# PCB-BI8-1x4SERCP_v08-16.net
KiCad netlist of a schematic drawn in EAGLE
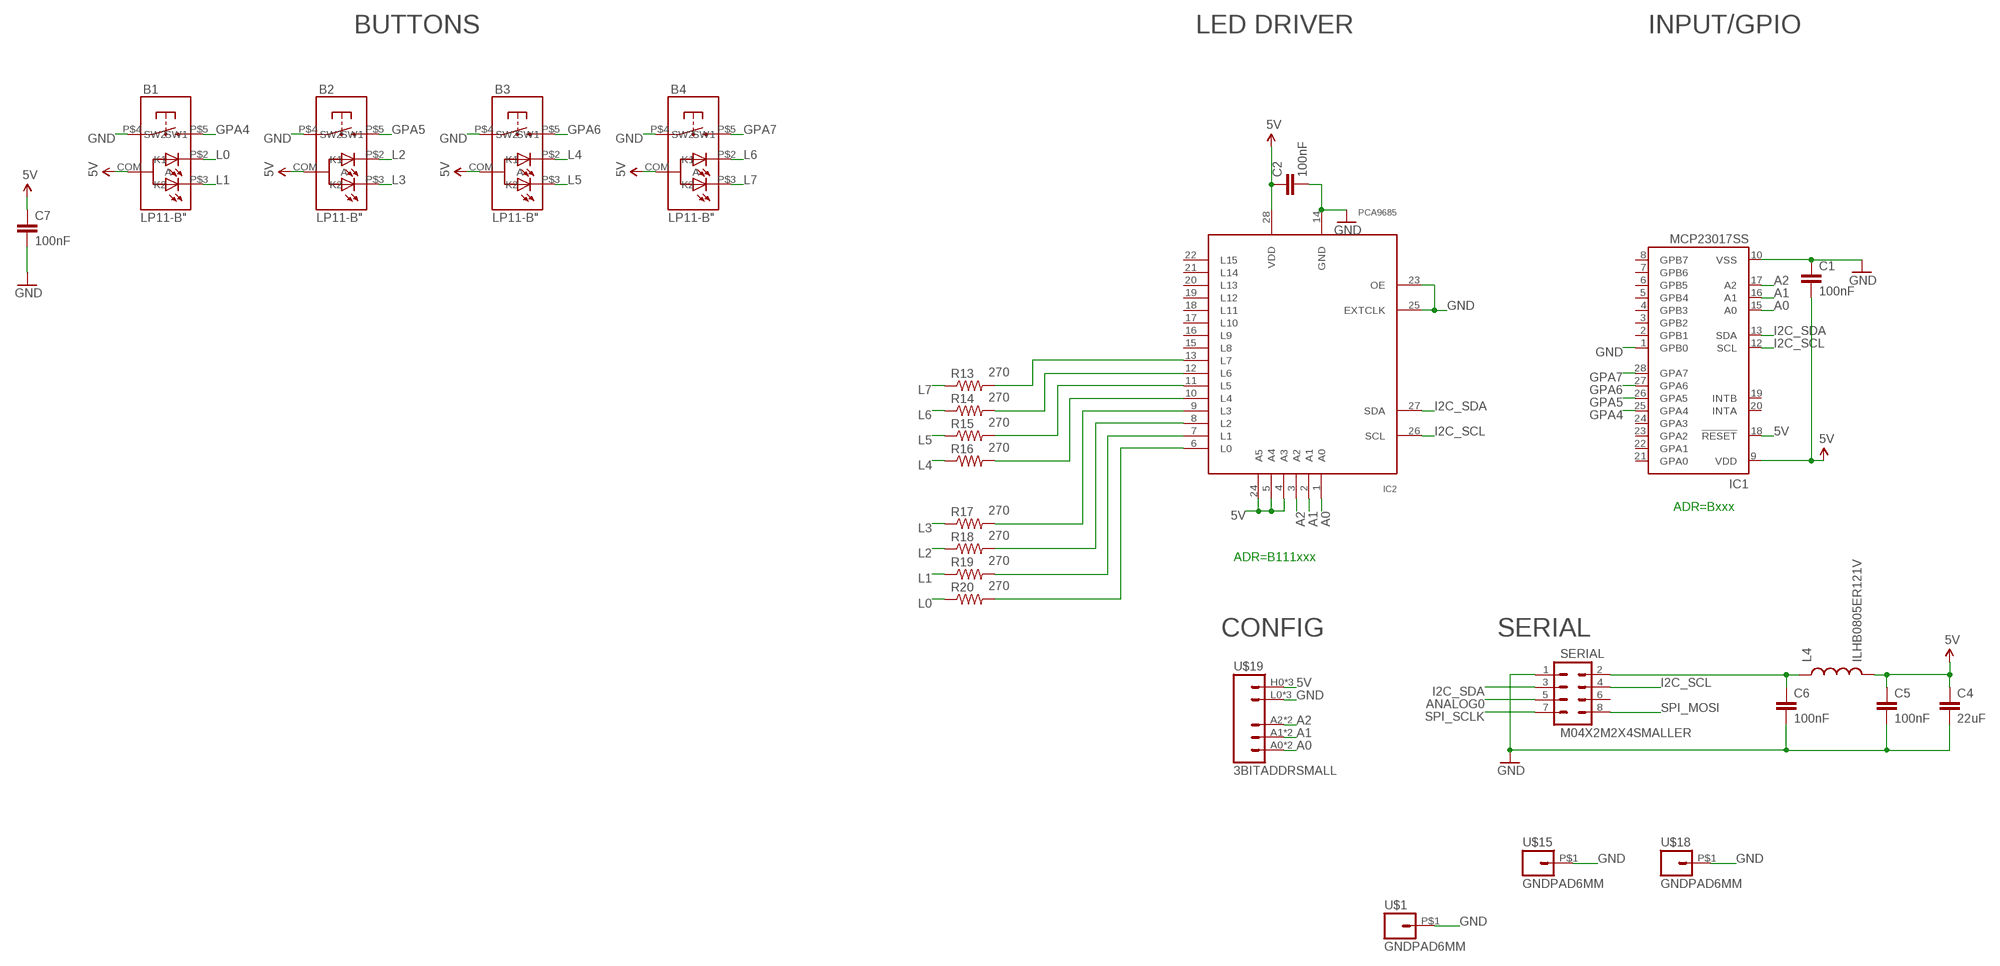
[diagram p0: schematic, sheet 1]

(export (version "E")
  (design (tool "Eeschema 10.0.6"))
  (components
    (comp (ref "B1")
      (value "LP11-B\"")
      (footprint "eagle-import:LP11")
      (libsource (lib "eagle-import") (part "LP11-B{dblquote}"))
    )
    (comp (ref "B2")
      (value "LP11-B\"")
      (footprint "eagle-import:LP11")
      (libsource (lib "eagle-import") (part "LP11-B{dblquote}"))
    )
    (comp (ref "B3")
      (value "LP11-B\"")
      (footprint "eagle-import:LP11")
      (libsource (lib "eagle-import") (part "LP11-B{dblquote}"))
    )
    (comp (ref "B4")
      (value "LP11-B\"")
      (footprint "eagle-import:LP11")
      (libsource (lib "eagle-import") (part "LP11-B{dblquote}"))
    )
    (comp (ref "C1")
      (value "100nF")
      (footprint "eagle-import:0603-CAP")
      (libsource (lib "eagle-import") (part "CAP0603-CAP"))
    )
    (comp (ref "C2")
      (value "100nF")
      (footprint "eagle-import:0603-CAP")
      (libsource (lib "eagle-import") (part "CAP0603-CAP"))
    )
    (comp (ref "C4")
      (value "22uF")
      (footprint "eagle-import:0805")
      (libsource (lib "eagle-import") (part "CAP0805"))
    )
    (comp (ref "C5")
      (value "100nF")
      (footprint "eagle-import:0603-CAP")
      (libsource (lib "eagle-import") (part "CAP0603-CAP"))
    )
    (comp (ref "C6")
      (value "100nF")
      (footprint "eagle-import:0603-CAP")
      (libsource (lib "eagle-import") (part "CAP0603-CAP"))
    )
    (comp (ref "C7")
      (value "100nF")
      (footprint "eagle-import:0603-CAP")
      (libsource (lib "eagle-import") (part "CAP0603-CAP"))
    )
    (comp (ref "IC1")
      (value "MCP23017SS")
      (footprint "eagle-import:SSOP28")
      (fields
        (field (name "MF") "MICROCHIP")
        (field (name "MPN") "MCP23017-E/SS")
        (field (name "MPN_1") "MCP23017-E/SS")
        (field (name "OC_FARNELL") "1467674")
        (field (name "OC_NEWARK") "31K2960")
      )
      (libsource (lib "eagle-import") (part "MCP23017SS"))
    )
    (comp (ref "IC2")
      (value "PCA9685")
      (footprint "eagle-import:TSSOP28")
      (libsource (lib "eagle-import") (part "PCA9685"))
    )
    (comp (ref "L4")
      (value "ILHB0805ER121V")
      (footprint "eagle-import:0805")
      (libsource (lib "eagle-import") (part "INDUCTOR0805"))
    )
    (comp (ref "R13")
      (value "270")
      (footprint "eagle-import:0603-RES")
      (libsource (lib "eagle-import") (part "RESISTOR0603-RES"))
    )
    (comp (ref "R14")
      (value "270")
      (footprint "eagle-import:0603-RES")
      (libsource (lib "eagle-import") (part "RESISTOR0603-RES"))
    )
    (comp (ref "R15")
      (value "270")
      (footprint "eagle-import:0603-RES")
      (libsource (lib "eagle-import") (part "RESISTOR0603-RES"))
    )
    (comp (ref "R16")
      (value "270")
      (footprint "eagle-import:0603-RES")
      (libsource (lib "eagle-import") (part "RESISTOR0603-RES"))
    )
    (comp (ref "R17")
      (value "270")
      (footprint "eagle-import:0603-RES")
      (libsource (lib "eagle-import") (part "RESISTOR0603-RES"))
    )
    (comp (ref "R18")
      (value "270")
      (footprint "eagle-import:0603-RES")
      (libsource (lib "eagle-import") (part "RESISTOR0603-RES"))
    )
    (comp (ref "R19")
      (value "270")
      (footprint "eagle-import:0603-RES")
      (libsource (lib "eagle-import") (part "RESISTOR0603-RES"))
    )
    (comp (ref "R20")
      (value "270")
      (footprint "eagle-import:0603-RES")
      (libsource (lib "eagle-import") (part "RESISTOR0603-RES"))
    )
    (comp (ref "SERIAL")
      (value "M04X2M2X4SMALLER")
      (footprint "eagle-import:M2X4SMALLER")
      (libsource (lib "eagle-import") (part "M04X2M2X4SMALLER"))
    )
    (comp (ref "U$1")
      (value "GNDPAD6MM")
      (footprint "eagle-import:3.2MMPAD6MM")
      (libsource (lib "eagle-import") (part "GNDPAD6MM"))
    )
    (comp (ref "U$15")
      (value "GNDPAD6MM")
      (footprint "eagle-import:3.2MMPAD6MM")
      (libsource (lib "eagle-import") (part "GNDPAD6MM"))
    )
    (comp (ref "U$18")
      (value "GNDPAD6MM")
      (footprint "eagle-import:3.2MMPAD6MM")
      (libsource (lib "eagle-import") (part "GNDPAD6MM"))
    )
    (comp (ref "U$19")
      (value "3BITADDRSMALL")
      (footprint "eagle-import:3BITADDR_SMALL")
      (libsource (lib "eagle-import") (part "3BITADDRSMALL"))
    )
  )
  (nets
    (net (code "1") (name "5V") (class "Default")
      (node (ref "B1") (pin "COM") (pinfunction "A_COM") (pintype "bidirectional"))
      (node (ref "B2") (pin "COM") (pinfunction "A_COM") (pintype "bidirectional"))
      (node (ref "B3") (pin "COM") (pinfunction "A_COM") (pintype "bidirectional"))
      (node (ref "B4") (pin "COM") (pinfunction "A_COM") (pintype "bidirectional"))
      (node (ref "C1") (pin "2") (pinfunction "2_2") (pintype "passive"))
      (node (ref "C2") (pin "1") (pinfunction "1_1") (pintype "passive"))
      (node (ref "C4") (pin "1") (pinfunction "1_1") (pintype "passive"))
      (node (ref "C5") (pin "1") (pinfunction "1_1") (pintype "passive"))
      (node (ref "C7") (pin "1") (pinfunction "1_1") (pintype "passive"))
      (node (ref "IC1") (pin "18") (pinfunction "~{RESET}_18") (pintype "input"))
      (node (ref "IC1") (pin "9") (pinfunction "VDD_9") (pintype "power_in"))
      (node (ref "IC2") (pin "24") (pinfunction "A5_24") (pintype "input"))
      (node (ref "IC2") (pin "28") (pinfunction "VDD_28") (pintype "power_in"))
      (node (ref "IC2") (pin "4") (pinfunction "A3_4") (pintype "input"))
      (node (ref "IC2") (pin "5") (pinfunction "A4_5") (pintype "input"))
      (node (ref "L4") (pin "2") (pinfunction "2_2") (pintype "passive"))
      (node (ref "U$19") (pin "H0") (pinfunction "VCC_H0") (pintype "passive"))
      (node (ref "U$19") (pin "H1") (pinfunction "VCC_H1") (pintype "passive"))
      (node (ref "U$19") (pin "H2") (pinfunction "VCC_H2") (pintype "passive"))
    )
    (net (code "2") (name "A0") (class "Default")
      (node (ref "IC1") (pin "15") (pinfunction "A0_15") (pintype "input"))
      (node (ref "IC2") (pin "1") (pinfunction "A0_1") (pintype "input"))
      (node (ref "U$19") (pin "A0") (pinfunction "A0_A0") (pintype "passive"))
      (node (ref "U$19") (pin "AS0") (pinfunction "A0_AS0") (pintype "passive"))
    )
    (net (code "3") (name "A1") (class "Default")
      (node (ref "IC1") (pin "16") (pinfunction "A1_16") (pintype "input"))
      (node (ref "IC2") (pin "2") (pinfunction "A1_2") (pintype "input"))
      (node (ref "U$19") (pin "A1") (pinfunction "A1_A1") (pintype "passive"))
      (node (ref "U$19") (pin "AS1") (pinfunction "A1_AS1") (pintype "passive"))
    )
    (net (code "4") (name "A2") (class "Default")
      (node (ref "IC1") (pin "17") (pinfunction "A2_17") (pintype "input"))
      (node (ref "IC2") (pin "3") (pinfunction "A2_3") (pintype "input"))
      (node (ref "U$19") (pin "A2") (pinfunction "A2_A2") (pintype "passive"))
      (node (ref "U$19") (pin "AS2") (pinfunction "A2_AS2") (pintype "passive"))
    )
    (net (code "5") (name "ANALOG0") (class "Default")
      (node (ref "SERIAL") (pin "5") (pinfunction "5_5") (pintype "passive"))
    )
    (net (code "6") (name "GND") (class "Default")
      (node (ref "B1") (pin "P$4") (pinfunction "SW1_P$4") (pintype "bidirectional"))
      (node (ref "B2") (pin "P$4") (pinfunction "SW1_P$4") (pintype "bidirectional"))
      (node (ref "B3") (pin "P$4") (pinfunction "SW1_P$4") (pintype "bidirectional"))
      (node (ref "B4") (pin "P$4") (pinfunction "SW1_P$4") (pintype "bidirectional"))
      (node (ref "C1") (pin "1") (pinfunction "1_1") (pintype "passive"))
      (node (ref "C2") (pin "2") (pinfunction "2_2") (pintype "passive"))
      (node (ref "C4") (pin "2") (pinfunction "2_2") (pintype "passive"))
      (node (ref "C5") (pin "2") (pinfunction "2_2") (pintype "passive"))
      (node (ref "C6") (pin "2") (pinfunction "2_2") (pintype "passive"))
      (node (ref "C7") (pin "2") (pinfunction "2_2") (pintype "passive"))
      (node (ref "IC1") (pin "1") (pinfunction "GPB0_1") (pintype "bidirectional"))
      (node (ref "IC1") (pin "10") (pinfunction "VSS_10") (pintype "power_in"))
      (node (ref "IC2") (pin "14") (pinfunction "GND_14") (pintype "power_in"))
      (node (ref "IC2") (pin "23") (pinfunction "OE_23") (pintype "input"))
      (node (ref "IC2") (pin "25") (pinfunction "EXTCLK_25") (pintype "input"))
      (node (ref "SERIAL") (pin "1") (pinfunction "1_1") (pintype "passive"))
      (node (ref "U$1") (pin "P$1") (pinfunction "1_P$1") (pintype "passive"))
      (node (ref "U$15") (pin "P$1") (pinfunction "1_P$1") (pintype "passive"))
      (node (ref "U$18") (pin "P$1") (pinfunction "1_P$1") (pintype "passive"))
      (node (ref "U$19") (pin "L0") (pinfunction "GND_L0") (pintype "passive"))
      (node (ref "U$19") (pin "L1") (pinfunction "GND_L1") (pintype "passive"))
      (node (ref "U$19") (pin "L2") (pinfunction "GND_L2") (pintype "passive"))
    )
    (net (code "7") (name "GPA4") (class "Default")
      (node (ref "B1") (pin "P$5") (pinfunction "SW2_P$5") (pintype "bidirectional"))
      (node (ref "IC1") (pin "25") (pinfunction "GPA4_25") (pintype "bidirectional"))
    )
    (net (code "8") (name "GPA5") (class "Default")
      (node (ref "B2") (pin "P$5") (pinfunction "SW2_P$5") (pintype "bidirectional"))
      (node (ref "IC1") (pin "26") (pinfunction "GPA5_26") (pintype "bidirectional"))
    )
    (net (code "9") (name "GPA6") (class "Default")
      (node (ref "B3") (pin "P$5") (pinfunction "SW2_P$5") (pintype "bidirectional"))
      (node (ref "IC1") (pin "27") (pinfunction "GPA6_27") (pintype "bidirectional"))
    )
    (net (code "10") (name "GPA7") (class "Default")
      (node (ref "B4") (pin "P$5") (pinfunction "SW2_P$5") (pintype "bidirectional"))
      (node (ref "IC1") (pin "28") (pinfunction "GPA7_28") (pintype "bidirectional"))
    )
    (net (code "11") (name "I2C_SCL") (class "Default")
      (node (ref "IC1") (pin "12") (pinfunction "SCL_12") (pintype "input"))
      (node (ref "IC2") (pin "26") (pinfunction "SCL_26") (pintype "input"))
      (node (ref "SERIAL") (pin "4") (pinfunction "4_4") (pintype "passive"))
    )
    (net (code "12") (name "I2C_SDA") (class "Default")
      (node (ref "IC1") (pin "13") (pinfunction "SDA_13") (pintype "bidirectional"))
      (node (ref "IC2") (pin "27") (pinfunction "SDA_27") (pintype "input"))
      (node (ref "SERIAL") (pin "3") (pinfunction "3_3") (pintype "passive"))
    )
    (net (code "13") (name "L0") (class "Default")
      (node (ref "B1") (pin "P$2") (pinfunction "K1_P$2") (pintype "bidirectional"))
      (node (ref "R20") (pin "1") (pinfunction "1_1") (pintype "passive"))
    )
    (net (code "14") (name "L1") (class "Default")
      (node (ref "B1") (pin "P$3") (pinfunction "K2_P$3") (pintype "bidirectional"))
      (node (ref "R19") (pin "1") (pinfunction "1_1") (pintype "passive"))
    )
    (net (code "15") (name "L2") (class "Default")
      (node (ref "B2") (pin "P$2") (pinfunction "K1_P$2") (pintype "bidirectional"))
      (node (ref "R18") (pin "1") (pinfunction "1_1") (pintype "passive"))
    )
    (net (code "16") (name "L3") (class "Default")
      (node (ref "B2") (pin "P$3") (pinfunction "K2_P$3") (pintype "bidirectional"))
      (node (ref "R17") (pin "1") (pinfunction "1_1") (pintype "passive"))
    )
    (net (code "17") (name "L4") (class "Default")
      (node (ref "B3") (pin "P$2") (pinfunction "K1_P$2") (pintype "bidirectional"))
      (node (ref "R16") (pin "1") (pinfunction "1_1") (pintype "passive"))
    )
    (net (code "18") (name "L5") (class "Default")
      (node (ref "B3") (pin "P$3") (pinfunction "K2_P$3") (pintype "bidirectional"))
      (node (ref "R15") (pin "1") (pinfunction "1_1") (pintype "passive"))
    )
    (net (code "19") (name "L6") (class "Default")
      (node (ref "B4") (pin "P$2") (pinfunction "K1_P$2") (pintype "bidirectional"))
      (node (ref "R14") (pin "1") (pinfunction "1_1") (pintype "passive"))
    )
    (net (code "20") (name "L7") (class "Default")
      (node (ref "B4") (pin "P$3") (pinfunction "K2_P$3") (pintype "bidirectional"))
      (node (ref "R13") (pin "1") (pinfunction "1_1") (pintype "passive"))
    )
    (net (code "21") (name "Net-(C6-Pad1)") (class "Default")
      (node (ref "C6") (pin "1") (pinfunction "1_1") (pintype "passive"))
      (node (ref "L4") (pin "1") (pinfunction "1_1") (pintype "passive"))
      (node (ref "SERIAL") (pin "2") (pinfunction "2_2") (pintype "passive"))
    )
    (net (code "22") (name "Net-(IC2-L0)") (class "Default")
      (node (ref "IC2") (pin "6") (pinfunction "L0_6") (pintype "output"))
      (node (ref "R20") (pin "2") (pinfunction "2_2") (pintype "passive"))
    )
    (net (code "23") (name "Net-(IC2-L1)") (class "Default")
      (node (ref "IC2") (pin "7") (pinfunction "L1_7") (pintype "output"))
      (node (ref "R19") (pin "2") (pinfunction "2_2") (pintype "passive"))
    )
    (net (code "24") (name "Net-(IC2-L2)") (class "Default")
      (node (ref "IC2") (pin "8") (pinfunction "L2_8") (pintype "output"))
      (node (ref "R18") (pin "2") (pinfunction "2_2") (pintype "passive"))
    )
    (net (code "25") (name "Net-(IC2-L3)") (class "Default")
      (node (ref "IC2") (pin "9") (pinfunction "L3_9") (pintype "output"))
      (node (ref "R17") (pin "2") (pinfunction "2_2") (pintype "passive"))
    )
    (net (code "26") (name "Net-(IC2-L4)") (class "Default")
      (node (ref "IC2") (pin "10") (pinfunction "L4_10") (pintype "output"))
      (node (ref "R16") (pin "2") (pinfunction "2_2") (pintype "passive"))
    )
    (net (code "27") (name "Net-(IC2-L5)") (class "Default")
      (node (ref "IC2") (pin "11") (pinfunction "L5_11") (pintype "output"))
      (node (ref "R15") (pin "2") (pinfunction "2_2") (pintype "passive"))
    )
    (net (code "28") (name "Net-(IC2-L6)") (class "Default")
      (node (ref "IC2") (pin "12") (pinfunction "L6_12") (pintype "output"))
      (node (ref "R14") (pin "2") (pinfunction "2_2") (pintype "passive"))
    )
    (net (code "29") (name "Net-(IC2-L7)") (class "Default")
      (node (ref "IC2") (pin "13") (pinfunction "L7_13") (pintype "output"))
      (node (ref "R13") (pin "2") (pinfunction "2_2") (pintype "passive"))
    )
    (net (code "30") (name "SPI_MOSI") (class "Default")
      (node (ref "SERIAL") (pin "8") (pinfunction "8_8") (pintype "passive"))
    )
    (net (code "31") (name "SPI_SCLK") (class "Default")
      (node (ref "SERIAL") (pin "7") (pinfunction "7_7") (pintype "passive"))
    )
    (net (code "32") (name "unconnected-(IC1-GPA0-Pad21)") (class "Default")
      (node (ref "IC1") (pin "21") (pinfunction "GPA0_21") (pintype "bidirectional"))
    )
    (net (code "33") (name "unconnected-(IC1-GPA1-Pad22)") (class "Default")
      (node (ref "IC1") (pin "22") (pinfunction "GPA1_22") (pintype "bidirectional"))
    )
    (net (code "34") (name "unconnected-(IC1-GPA2-Pad23)") (class "Default")
      (node (ref "IC1") (pin "23") (pinfunction "GPA2_23") (pintype "bidirectional"))
    )
    (net (code "35") (name "unconnected-(IC1-GPA3-Pad24)") (class "Default")
      (node (ref "IC1") (pin "24") (pinfunction "GPA3_24") (pintype "bidirectional"))
    )
    (net (code "36") (name "unconnected-(IC1-GPB1-Pad2)") (class "Default")
      (node (ref "IC1") (pin "2") (pinfunction "GPB1_2") (pintype "bidirectional"))
    )
    (net (code "37") (name "unconnected-(IC1-GPB2-Pad3)") (class "Default")
      (node (ref "IC1") (pin "3") (pinfunction "GPB2_3") (pintype "bidirectional"))
    )
    (net (code "38") (name "unconnected-(IC1-GPB3-Pad4)") (class "Default")
      (node (ref "IC1") (pin "4") (pinfunction "GPB3_4") (pintype "bidirectional"))
    )
    (net (code "39") (name "unconnected-(IC1-GPB4-Pad5)") (class "Default")
      (node (ref "IC1") (pin "5") (pinfunction "GPB4_5") (pintype "bidirectional"))
    )
    (net (code "40") (name "unconnected-(IC1-GPB5-Pad6)") (class "Default")
      (node (ref "IC1") (pin "6") (pinfunction "GPB5_6") (pintype "bidirectional"))
    )
    (net (code "41") (name "unconnected-(IC1-GPB6-Pad7)") (class "Default")
      (node (ref "IC1") (pin "7") (pinfunction "GPB6_7") (pintype "bidirectional"))
    )
    (net (code "42") (name "unconnected-(IC1-GPB7-Pad8)") (class "Default")
      (node (ref "IC1") (pin "8") (pinfunction "GPB7_8") (pintype "bidirectional"))
    )
    (net (code "43") (name "unconnected-(IC1-INTA-Pad20)") (class "Default")
      (node (ref "IC1") (pin "20") (pinfunction "INTA_20") (pintype "output"))
    )
    (net (code "44") (name "unconnected-(IC1-INTB-Pad19)") (class "Default")
      (node (ref "IC1") (pin "19") (pinfunction "INTB_19") (pintype "output"))
    )
    (net (code "45") (name "unconnected-(IC2-L8-Pad15)") (class "Default")
      (node (ref "IC2") (pin "15") (pinfunction "L8_15") (pintype "output"))
    )
    (net (code "46") (name "unconnected-(IC2-L9-Pad16)") (class "Default")
      (node (ref "IC2") (pin "16") (pinfunction "L9_16") (pintype "output"))
    )
    (net (code "47") (name "unconnected-(IC2-L10-Pad17)") (class "Default")
      (node (ref "IC2") (pin "17") (pinfunction "L10_17") (pintype "output"))
    )
    (net (code "48") (name "unconnected-(IC2-L11-Pad18)") (class "Default")
      (node (ref "IC2") (pin "18") (pinfunction "L11_18") (pintype "output"))
    )
    (net (code "49") (name "unconnected-(IC2-L12-Pad19)") (class "Default")
      (node (ref "IC2") (pin "19") (pinfunction "L12_19") (pintype "output"))
    )
    (net (code "50") (name "unconnected-(IC2-L13-Pad20)") (class "Default")
      (node (ref "IC2") (pin "20") (pinfunction "L13_20") (pintype "output"))
    )
    (net (code "51") (name "unconnected-(IC2-L14-Pad21)") (class "Default")
      (node (ref "IC2") (pin "21") (pinfunction "L14_21") (pintype "output"))
    )
    (net (code "52") (name "unconnected-(IC2-L15-Pad22)") (class "Default")
      (node (ref "IC2") (pin "22") (pinfunction "L15_22") (pintype "output"))
    )
    (net (code "53") (name "unconnected-(SERIAL-Pad6)") (class "Default")
      (node (ref "SERIAL") (pin "6") (pinfunction "6_6") (pintype "passive"))
    )
  )
)
